# 06-7Segment_MAX7219.net
KiCad netlist of a schematic drawn in Altium Designer
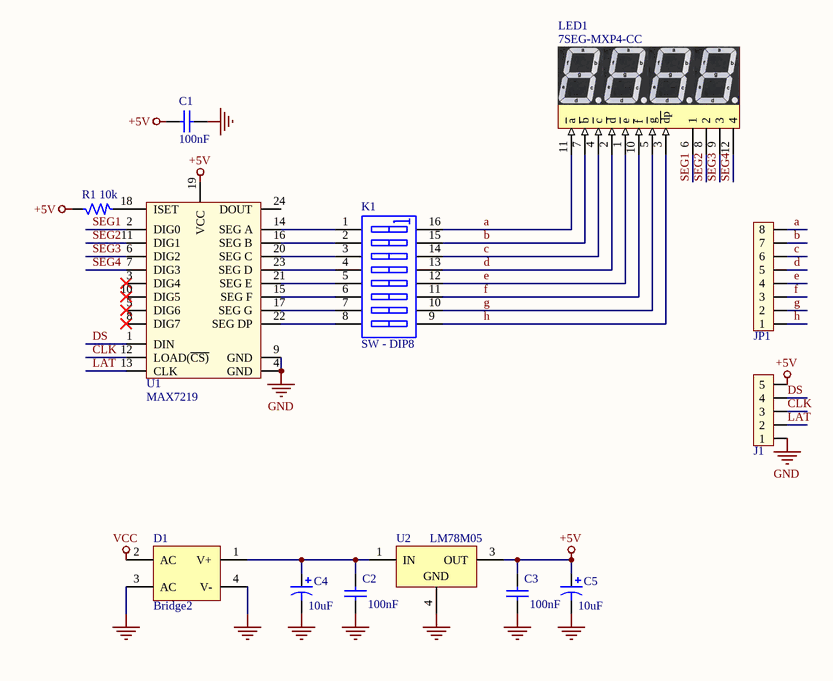
[diagram p0: 06-7Segment(MAX7219).SchDoc]

(export (version "E")
  (design (tool "Eeschema 10.0.6"))
  (components
    (comp (ref "C1")
      (value "100nF")
      (footprint "RAD-0.3")
      (description "Capacitor")
      (fields (field (name "Comment") "104") (field (name "PUBLISHER") "Altium Limited"))
      (libsource (lib "Miscellaneous Devices") (part "Cap"))
    )
    (comp (ref "C2")
      (value "100nF")
      (footprint "RAD-0.3")
      (description "Capacitor")
      (fields (field (name "Comment") "104") (field (name "PUBLISHER") "Altium Limited"))
      (libsource (lib "Miscellaneous Devices") (part "Cap"))
    )
    (comp (ref "C3")
      (value "100nF")
      (footprint "RAD-0.3")
      (description "Capacitor")
      (fields (field (name "Comment") "104") (field (name "PUBLISHER") "Altium Limited"))
      (libsource (lib "Miscellaneous Devices") (part "Cap"))
    )
    (comp (ref "C4")
      (value "10uF")
      (footprint "RB7.6-15")
      (description "Polarized Capacitor (Radial)")
      (fields (field (name "Comment") "10uF/16V") (field (name "PUBLISHER") "Altium Limited"))
      (libsource (lib "Miscellaneous Devices") (part "Cap Pol1"))
    )
    (comp (ref "C5")
      (value "10uF")
      (footprint "RB7.6-15")
      (description "Polarized Capacitor (Radial)")
      (fields (field (name "Comment") "10uF/16V") (field (name "PUBLISHER") "Altium Limited"))
      (libsource (lib "Miscellaneous Devices") (part "Cap Pol1"))
    )
    (comp (ref "D1")
      (value "Bridge2")
      (footprint "D-46_6A")
      (description "Diode Bridge")
      (fields (field (name "PUBLISHER") "Altium Limited"))
      (libsource (lib "Miscellaneous Devices") (part "Bridge2"))
    )
    (comp (ref "J1") (value "JP5") (footprint "JP5") (libsource (lib "syhaunguyen") (part "JP5")))
    (comp (ref "JP1") (value "JP8 PIN") (footprint "JP8-2.54") (libsource (lib "syhaunguyen") (part "JP8")))
    (comp (ref "K1")
      (value "SW - DIP8")
      (footprint "SW-DIP-16")
      (description "DIP Switch, 8 Position, SPST")
      (libsource (lib "syhaunguyen") (part "SWDIP-8"))
    )
    (comp (ref "LED1")
      (value "7SEG-MXP4-CC")
      (footprint "7seg4 - 0.36 GREEN")
      (description "Four 7-segment led")
      (libsource (lib "Dlib") (part "7SEG-MXP4-CA"))
    )
    (comp (ref "R1")
      (value "10k")
      (footprint "R-0805")
      (description "Resistor 1/4W")
      (libsource (lib "syhaunguyen") (part "R"))
    )
    (comp (ref "U1")
      (value "MAX7219")
      (footprint "SOIC-24-W")
      (libsource (lib "doAnTotNghiep2017Lib") (part "MAX7219"))
    )
    (comp (ref "U2")
      (value "LM78M05")
      (footprint "NDP0003B_M")
      (description "3-Terminal Positive Voltage Regulators, 3-pin TO-252")
      (fields (field (name "MANUFACTURER") "Texas Instruments") (field (name "Comment") "LM78M05CDTX"))
      (libsource (lib "Altium Content Vault") (part "CMP-0062-00204-3"))
    )
  )
  (nets
    (net (code "1") (name "+5V") (class "Default")
      (node (ref "C1") (pin "1") (pinfunction "1_1") (pintype "passive"))
      (node (ref "C3") (pin "1") (pinfunction "1_1") (pintype "passive"))
      (node (ref "C5") (pin "1") (pinfunction "1_1") (pintype "passive"))
      (node (ref "J1") (pin "5") (pinfunction "5_5") (pintype "passive"))
      (node (ref "R1") (pin "1") (pinfunction "1_1") (pintype "passive"))
      (node (ref "U1") (pin "19") (pinfunction "VCC_19") (pintype "passive"))
      (node (ref "U2") (pin "3") (pinfunction "OUT_3") (pintype "power_in"))
    )
    (net (code "2") (name "/CLK") (class "Default")
      (node (ref "J1") (pin "3") (pinfunction "3_3") (pintype "passive"))
      (node (ref "U1") (pin "12") (pinfunction "LOAD(~{CS)}_12") (pintype "passive"))
    )
    (net (code "3") (name "/DS") (class "Default")
      (node (ref "J1") (pin "4") (pinfunction "4_4") (pintype "passive"))
      (node (ref "U1") (pin "1") (pinfunction "DIN_1") (pintype "passive"))
    )
    (net (code "4") (name "/LAT") (class "Default")
      (node (ref "J1") (pin "2") (pinfunction "2_2") (pintype "passive"))
      (node (ref "U1") (pin "13") (pinfunction "CLK_13") (pintype "passive"))
    )
    (net (code "5") (name "/SEG1") (class "Default")
      (node (ref "LED1") (pin "6") (pinfunction "1_6") (pintype "power_in"))
      (node (ref "U1") (pin "2") (pinfunction "DIG0_2") (pintype "passive"))
    )
    (net (code "6") (name "/SEG2") (class "Default")
      (node (ref "LED1") (pin "8") (pinfunction "2_8") (pintype "power_in"))
      (node (ref "U1") (pin "11") (pinfunction "DIG1_11") (pintype "passive"))
    )
    (net (code "7") (name "/SEG3") (class "Default")
      (node (ref "LED1") (pin "9") (pinfunction "3_9") (pintype "power_in"))
      (node (ref "U1") (pin "6") (pinfunction "DIG2_6") (pintype "passive"))
    )
    (net (code "8") (name "/SEG4") (class "Default")
      (node (ref "LED1") (pin "12") (pinfunction "4_12") (pintype "power_in"))
      (node (ref "U1") (pin "7") (pinfunction "DIG3_7") (pintype "passive"))
    )
    (net (code "9") (name "/a") (class "Default")
      (node (ref "JP1") (pin "8") (pinfunction "8_8") (pintype "passive"))
      (node (ref "K1") (pin "16") (pinfunction "B1_16") (pintype "passive"))
      (node (ref "LED1") (pin "11") (pinfunction "~{a}_11") (pintype "input"))
    )
    (net (code "10") (name "/b") (class "Default")
      (node (ref "JP1") (pin "7") (pinfunction "7_7") (pintype "passive"))
      (node (ref "K1") (pin "15") (pinfunction "B2_15") (pintype "passive"))
      (node (ref "LED1") (pin "7") (pinfunction "~{b}_7") (pintype "input"))
    )
    (net (code "11") (name "/c") (class "Default")
      (node (ref "JP1") (pin "6") (pinfunction "6_6") (pintype "passive"))
      (node (ref "K1") (pin "14") (pinfunction "B3_14") (pintype "passive"))
      (node (ref "LED1") (pin "4") (pinfunction "~{c}_4") (pintype "input"))
    )
    (net (code "12") (name "/d") (class "Default")
      (node (ref "JP1") (pin "5") (pinfunction "5_5") (pintype "passive"))
      (node (ref "K1") (pin "13") (pinfunction "B4_13") (pintype "passive"))
      (node (ref "LED1") (pin "2") (pinfunction "~{d}_2") (pintype "input"))
    )
    (net (code "13") (name "/e") (class "Default")
      (node (ref "JP1") (pin "4") (pinfunction "4_4") (pintype "passive"))
      (node (ref "K1") (pin "12") (pinfunction "B5_12") (pintype "passive"))
      (node (ref "LED1") (pin "1") (pinfunction "~{e}_1") (pintype "input"))
    )
    (net (code "14") (name "/f") (class "Default")
      (node (ref "JP1") (pin "3") (pinfunction "3_3") (pintype "passive"))
      (node (ref "K1") (pin "11") (pinfunction "B6_11") (pintype "passive"))
      (node (ref "LED1") (pin "10") (pinfunction "~{f}_10") (pintype "input"))
    )
    (net (code "15") (name "/g") (class "Default")
      (node (ref "JP1") (pin "2") (pinfunction "2_2") (pintype "passive"))
      (node (ref "K1") (pin "10") (pinfunction "B7_10") (pintype "passive"))
      (node (ref "LED1") (pin "5") (pinfunction "~{g}_5") (pintype "input"))
    )
    (net (code "16") (name "/h") (class "Default")
      (node (ref "JP1") (pin "1") (pinfunction "1_1") (pintype "passive"))
      (node (ref "K1") (pin "9") (pinfunction "B8_9") (pintype "passive"))
      (node (ref "LED1") (pin "3") (pinfunction "~{dp}_3") (pintype "input"))
    )
    (net (code "17") (name "GND") (class "Default")
      (node (ref "C1") (pin "2") (pinfunction "2_2") (pintype "passive"))
      (node (ref "C2") (pin "2") (pinfunction "2_2") (pintype "passive"))
      (node (ref "C3") (pin "2") (pinfunction "2_2") (pintype "passive"))
      (node (ref "C4") (pin "2") (pinfunction "2_2") (pintype "passive"))
      (node (ref "C5") (pin "2") (pinfunction "2_2") (pintype "passive"))
      (node (ref "D1") (pin "3") (pinfunction "AC_3") (pintype "passive"))
      (node (ref "D1") (pin "4") (pinfunction "V-_4") (pintype "passive"))
      (node (ref "J1") (pin "1") (pinfunction "1_1") (pintype "passive"))
      (node (ref "U1") (pin "4") (pinfunction "GND_4") (pintype "passive"))
      (node (ref "U1") (pin "9") (pinfunction "GND_9") (pintype "passive"))
      (node (ref "U2") (pin "4") (pinfunction "GND_4") (pintype "power_in"))
    )
    (net (code "18") (name "Net-(D1-V+)") (class "Default")
      (node (ref "C2") (pin "1") (pinfunction "1_1") (pintype "passive"))
      (node (ref "C4") (pin "1") (pinfunction "1_1") (pintype "passive"))
      (node (ref "D1") (pin "1") (pinfunction "V+_1") (pintype "passive"))
      (node (ref "U2") (pin "1") (pinfunction "IN_1") (pintype "power_in"))
    )
    (net (code "19") (name "Net-(K1-A1)") (class "Default")
      (node (ref "K1") (pin "1") (pinfunction "A1_1") (pintype "passive"))
      (node (ref "U1") (pin "14") (pinfunction "SEG_A_14") (pintype "passive"))
    )
    (net (code "20") (name "Net-(K1-A2)") (class "Default")
      (node (ref "K1") (pin "2") (pinfunction "A2_2") (pintype "passive"))
      (node (ref "U1") (pin "16") (pinfunction "SEG_B_16") (pintype "passive"))
    )
    (net (code "21") (name "Net-(K1-A3)") (class "Default")
      (node (ref "K1") (pin "3") (pinfunction "A3_3") (pintype "passive"))
      (node (ref "U1") (pin "20") (pinfunction "SEG_C_20") (pintype "passive"))
    )
    (net (code "22") (name "Net-(K1-A4)") (class "Default")
      (node (ref "K1") (pin "4") (pinfunction "A4_4") (pintype "passive"))
      (node (ref "U1") (pin "23") (pinfunction "SEG_D_23") (pintype "passive"))
    )
    (net (code "23") (name "Net-(K1-A5)") (class "Default")
      (node (ref "K1") (pin "5") (pinfunction "A5_5") (pintype "passive"))
      (node (ref "U1") (pin "21") (pinfunction "SEG_E_21") (pintype "passive"))
    )
    (net (code "24") (name "Net-(K1-A6)") (class "Default")
      (node (ref "K1") (pin "6") (pinfunction "A6_6") (pintype "passive"))
      (node (ref "U1") (pin "15") (pinfunction "SEG_F_15") (pintype "passive"))
    )
    (net (code "25") (name "Net-(K1-A7)") (class "Default")
      (node (ref "K1") (pin "7") (pinfunction "A7_7") (pintype "passive"))
      (node (ref "U1") (pin "17") (pinfunction "SEG_G_17") (pintype "passive"))
    )
    (net (code "26") (name "Net-(K1-A8)") (class "Default")
      (node (ref "K1") (pin "8") (pinfunction "A8_8") (pintype "passive"))
      (node (ref "U1") (pin "22") (pinfunction "SEG_DP_22") (pintype "passive"))
    )
    (net (code "27") (name "Net-(U1-ISET)") (class "Default")
      (node (ref "R1") (pin "2") (pinfunction "2_2") (pintype "passive"))
      (node (ref "U1") (pin "18") (pinfunction "ISET_18") (pintype "passive"))
    )
    (net (code "28") (name "VCC") (class "Default")
      (node (ref "D1") (pin "2") (pinfunction "AC_2") (pintype "passive"))
    )
    (net (code "29") (name "unconnected-(U1-DIG4-Pad3)") (class "Default")
      (node (ref "U1") (pin "3") (pinfunction "DIG4_3") (pintype "passive+no_connect"))
    )
    (net (code "30") (name "unconnected-(U1-DIG5-Pad10)") (class "Default")
      (node (ref "U1") (pin "10") (pinfunction "DIG5_10") (pintype "passive+no_connect"))
    )
    (net (code "31") (name "unconnected-(U1-DIG6-Pad5)") (class "Default")
      (node (ref "U1") (pin "5") (pinfunction "DIG6_5") (pintype "passive+no_connect"))
    )
    (net (code "32") (name "unconnected-(U1-DIG7-Pad8)") (class "Default")
      (node (ref "U1") (pin "8") (pinfunction "DIG7_8") (pintype "passive+no_connect"))
    )
    (net (code "33") (name "unconnected-(U1-DOUT-Pad24)") (class "Default")
      (node (ref "U1") (pin "24") (pinfunction "DOUT_24") (pintype "passive"))
    )
  )
)
